# Voltage_Reg.net
KiCad netlist of a schematic drawn in Altium Designer
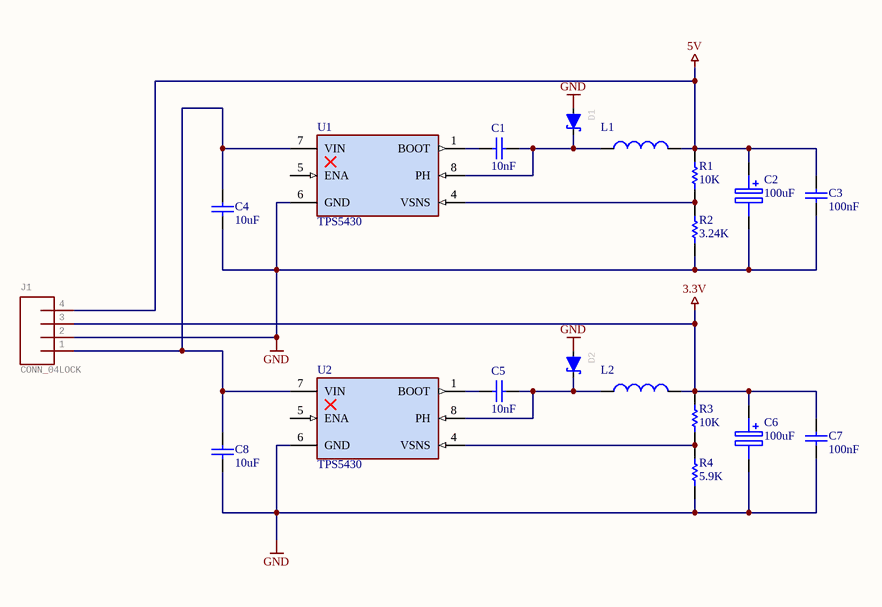
[diagram p0: Voltage Reg.SchDoc]

(export (version "E")
  (design (tool "Eeschema 10.0.6"))
  (components
    (comp (ref "C1")
      (value "10nF")
      (footprint "CAPC1608X90X35ML10T15")
      (description "CAP 10nF")
      (libsource (lib "Hwa Chong Institution") (part "CAPACITOR0603"))
    )
    (comp (ref "C2")
      (value "100uF")
      (footprint "CAPPM7344X310N")
      (description "25V 100UF ±20% TAJE107M025RNJ")
      (fields
        (field (name "MANUFACTURER_PART_NUMBER") "TAJD686K010R")
        (field (name "Comment") "TAJE107M025RNJ")
      )
      (libsource (lib "Hwa Chong Institution") (part "EIA7343"))
    )
    (comp (ref "C3")
      (value "100nF")
      (footprint "CAPC1608X90X35ML10T15")
      (description "CAP 100nF")
      (libsource (lib "Hwa Chong Institution") (part "CAPACITOR0603"))
    )
    (comp (ref "C4")
      (value "10uF")
      (footprint "CAPC1608X90X35ML10T15")
      (description "CAP 10uF")
      (libsource (lib "Hwa Chong Institution") (part "CAPACITOR0603"))
    )
    (comp (ref "C5")
      (value "10nF")
      (footprint "CAPC1608X90X35ML10T15")
      (description "CAP 10nF")
      (libsource (lib "Hwa Chong Institution") (part "CAPACITOR0603"))
    )
    (comp (ref "C6")
      (value "100uF")
      (footprint "CAPPM7344X310N")
      (description "25V 100UF ±20% TAJE107M025RNJ")
      (fields
        (field (name "MANUFACTURER_PART_NUMBER") "TAJD686K010R")
        (field (name "Comment") "TAJE107M025RNJ")
      )
      (libsource (lib "Hwa Chong Institution") (part "EIA7343"))
    )
    (comp (ref "C7")
      (value "100nF")
      (footprint "CAPC1608X90X35ML10T15")
      (description "CAP 100nF")
      (libsource (lib "Hwa Chong Institution") (part "CAPACITOR0603"))
    )
    (comp (ref "C8")
      (value "10uF")
      (footprint "CAPC1608X90X35ML10T15")
      (description "CAP 10uF")
      (libsource (lib "Hwa Chong Institution") (part "CAPACITOR0603"))
    )
    (comp (ref "D1")
      (value "Schotty Diode")
      (footprint "SMA-DIODE")
      (description "SMD")
      (libsource (lib "Hwa Chong Institution") (part "Schotty Diode"))
    )
    (comp (ref "D2")
      (value "Schotty Diode")
      (footprint "SMA-DIODE")
      (description "SMD")
      (libsource (lib "Hwa Chong Institution") (part "Schotty Diode"))
    )
    (comp (ref "J1")
      (value "CONN_04LOCK")
      (footprint "1X04_LOCK")
      (libsource (lib "Hwa Chong Institution") (part "CONN_04LOCK"))
    )
    (comp (ref "L1")
      (value "10Uh")
      (footprint "SWPA8040")
      (description "Inductor for 5V & 3.3V Buck")
      (libsource (lib "Hwa Chong Institution") (part "10Uh"))
    )
    (comp (ref "L2")
      (value "10Uh")
      (footprint "SWPA8040")
      (description "Inductor for 5V & 3.3V Buck")
      (libsource (lib "Hwa Chong Institution") (part "10Uh"))
    )
    (comp (ref "R1")
      (value "10K")
      (footprint "RESISTOR0603")
      (description "RES 10K 0603")
      (libsource (lib "Hwa Chong Institution") (part "RESISTOR0603"))
    )
    (comp (ref "R2")
      (value "3.24K")
      (footprint "RESISTOR0603")
      (description "RES 3.24K 0603")
      (libsource (lib "Hwa Chong Institution") (part "RESISTOR0603"))
    )
    (comp (ref "R3")
      (value "10K")
      (footprint "RESISTOR0603")
      (description "RES 10K 0603")
      (libsource (lib "Hwa Chong Institution") (part "RESISTOR0603"))
    )
    (comp (ref "R4")
      (value "5.9K")
      (footprint "RESISTOR0603")
      (description "RES 5.9K 0603")
      (libsource (lib "Hwa Chong Institution") (part "RESISTOR0603"))
    )
    (comp (ref "U1")
      (value "TPS5430")
      (footprint "FP-DDA0008J-MFG")
      (description "Step Down Converter")
      (libsource (lib "Hwa Chong Institution") (part "TPS5430"))
    )
    (comp (ref "U2")
      (value "TPS5430")
      (footprint "FP-DDA0008J-MFG")
      (description "Step Down Converter")
      (libsource (lib "Hwa Chong Institution") (part "TPS5430"))
    )
  )
  (nets
    (net (code "1") (name "3.3V") (class "Default")
      (node (ref "C6") (pin "1") (pinfunction "+_1") (pintype "passive"))
      (node (ref "C7") (pin "2") (pinfunction "2_2") (pintype "passive"))
      (node (ref "J1") (pin "3") (pinfunction "3_3") (pintype "passive"))
      (node (ref "L2") (pin "P2") (pinfunction "2_P2") (pintype "passive"))
      (node (ref "R3") (pin "2") (pinfunction "2_2") (pintype "passive"))
    )
    (net (code "2") (name "5V") (class "Default")
      (node (ref "C2") (pin "1") (pinfunction "+_1") (pintype "passive"))
      (node (ref "C3") (pin "2") (pinfunction "2_2") (pintype "passive"))
      (node (ref "J1") (pin "4") (pinfunction "4_4") (pintype "passive"))
      (node (ref "L1") (pin "P2") (pinfunction "2_P2") (pintype "passive"))
      (node (ref "R1") (pin "2") (pinfunction "2_2") (pintype "passive"))
    )
    (net (code "3") (name "GND") (class "Default")
      (node (ref "C2") (pin "2") (pinfunction "-_2") (pintype "passive"))
      (node (ref "C3") (pin "1") (pinfunction "1_1") (pintype "passive"))
      (node (ref "C4") (pin "1") (pinfunction "1_1") (pintype "passive"))
      (node (ref "C6") (pin "2") (pinfunction "-_2") (pintype "passive"))
      (node (ref "C7") (pin "1") (pinfunction "1_1") (pintype "passive"))
      (node (ref "C8") (pin "1") (pinfunction "1_1") (pintype "passive"))
      (node (ref "D1") (pin "1") (pinfunction "1_1") (pintype "passive"))
      (node (ref "D2") (pin "1") (pinfunction "1_1") (pintype "passive"))
      (node (ref "J1") (pin "2") (pinfunction "2_2") (pintype "passive"))
      (node (ref "R2") (pin "1") (pinfunction "1_1") (pintype "passive"))
      (node (ref "R4") (pin "1") (pinfunction "1_1") (pintype "passive"))
      (node (ref "U1") (pin "6") (pinfunction "GND_6") (pintype "power_in"))
      (node (ref "U2") (pin "6") (pinfunction "GND_6") (pintype "power_in"))
    )
    (net (code "4") (name "Net-(L1-1)") (class "Default")
      (node (ref "C1") (pin "1") (pinfunction "1_1") (pintype "passive"))
      (node (ref "D1") (pin "2") (pinfunction "2_2") (pintype "passive"))
      (node (ref "L1") (pin "P1") (pinfunction "1_P1") (pintype "passive"))
      (node (ref "U1") (pin "8") (pinfunction "PH_8") (pintype "input"))
    )
    (net (code "5") (name "Net-(L2-1)") (class "Default")
      (node (ref "C5") (pin "1") (pinfunction "1_1") (pintype "passive"))
      (node (ref "D2") (pin "2") (pinfunction "2_2") (pintype "passive"))
      (node (ref "L2") (pin "P1") (pinfunction "1_P1") (pintype "passive"))
      (node (ref "U2") (pin "8") (pinfunction "PH_8") (pintype "input"))
    )
    (net (code "6") (name "Net-(U1-BOOT)") (class "Default")
      (node (ref "C1") (pin "2") (pinfunction "2_2") (pintype "passive"))
      (node (ref "U1") (pin "1") (pinfunction "BOOT_1") (pintype "output"))
    )
    (net (code "7") (name "Net-(U1-VIN)") (class "Default")
      (node (ref "C4") (pin "2") (pinfunction "2_2") (pintype "passive"))
      (node (ref "C8") (pin "2") (pinfunction "2_2") (pintype "passive"))
      (node (ref "J1") (pin "1") (pinfunction "1_1") (pintype "passive"))
      (node (ref "U1") (pin "7") (pinfunction "VIN_7") (pintype "power_in"))
      (node (ref "U2") (pin "7") (pinfunction "VIN_7") (pintype "power_in"))
    )
    (net (code "8") (name "Net-(U1-VSNS)") (class "Default")
      (node (ref "R1") (pin "1") (pinfunction "1_1") (pintype "passive"))
      (node (ref "R2") (pin "2") (pinfunction "2_2") (pintype "passive"))
      (node (ref "U1") (pin "4") (pinfunction "VSNS_4") (pintype "input"))
    )
    (net (code "9") (name "Net-(U2-BOOT)") (class "Default")
      (node (ref "C5") (pin "2") (pinfunction "2_2") (pintype "passive"))
      (node (ref "U2") (pin "1") (pinfunction "BOOT_1") (pintype "output"))
    )
    (net (code "10") (name "Net-(U2-VSNS)") (class "Default")
      (node (ref "R3") (pin "1") (pinfunction "1_1") (pintype "passive"))
      (node (ref "R4") (pin "2") (pinfunction "2_2") (pintype "passive"))
      (node (ref "U2") (pin "4") (pinfunction "VSNS_4") (pintype "input"))
    )
    (net (code "11") (name "unconnected-(U1-ENA-Pad5)") (class "Default")
      (node (ref "U1") (pin "5") (pinfunction "ENA_5") (pintype "input"))
    )
    (net (code "12") (name "unconnected-(U2-ENA-Pad5)") (class "Default")
      (node (ref "U2") (pin "5") (pinfunction "ENA_5") (pintype "input"))
    )
  )
)
